# powerstrip.net
KiCad netlist of a schematic drawn in EAGLE
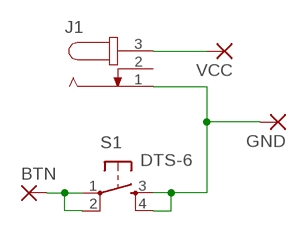
[diagram p0: schematic, sheet 1]

(export (version "E")
  (design (tool "Eeschema 10.0.6"))
  (components
    (comp (ref "BTN")
      (value "WIREPADSMD2,54-5,08")
      (footprint "eagle-import:SMD2,54-5,08")
      (libsource (lib "eagle-import") (part "WIREPADSMD2,54-5,08"))
    )
    (comp (ref "GND")
      (value "WIREPADSMD2,54-5,08")
      (footprint "eagle-import:SMD2,54-5,08")
      (libsource (lib "eagle-import") (part "WIREPADSMD2,54-5,08"))
    )
    (comp (ref "J1")
      (value "PC-GK210")
      (footprint "eagle-import:PC-GK21")
      (libsource (lib "eagle-import") (part "PC-GK210"))
    )
    (comp (ref "S1")
      (value "DTS-6")
      (footprint "eagle-import:DTS-6")
      (libsource (lib "eagle-import") (part "DTS-6"))
    )
    (comp (ref "VCC")
      (value "WIREPADSMD2,54-5,08")
      (footprint "eagle-import:SMD2,54-5,08")
      (libsource (lib "eagle-import") (part "WIREPADSMD2,54-5,08"))
    )
  )
  (nets
    (net (code "1") (name "Net-(BTN-P)") (class "Default")
      (node (ref "BTN") (pin "1") (pinfunction "P_1") (pintype "passive"))
      (node (ref "S1") (pin "1") (pinfunction "1_1") (pintype "passive"))
      (node (ref "S1") (pin "2") (pinfunction "2_2") (pintype "passive"))
    )
    (net (code "2") (name "Net-(GND-P)") (class "Default")
      (node (ref "GND") (pin "1") (pinfunction "P_1") (pintype "passive"))
      (node (ref "J1") (pin "1") (pinfunction "1_1") (pintype "passive"))
      (node (ref "S1") (pin "3") (pinfunction "3_3") (pintype "passive"))
      (node (ref "S1") (pin "4") (pinfunction "4_4") (pintype "passive"))
    )
    (net (code "3") (name "Net-(VCC-P)") (class "Default")
      (node (ref "J1") (pin "3") (pinfunction "3_3") (pintype "passive"))
      (node (ref "VCC") (pin "1") (pinfunction "P_1") (pintype "passive"))
    )
    (net (code "4") (name "unconnected-(J1-Pad2)") (class "Default")
      (node (ref "J1") (pin "2") (pinfunction "2_2") (pintype "passive"))
    )
  )
)
